# LiFePO4wered-USB.net
KiCad netlist of a schematic drawn in EAGLE
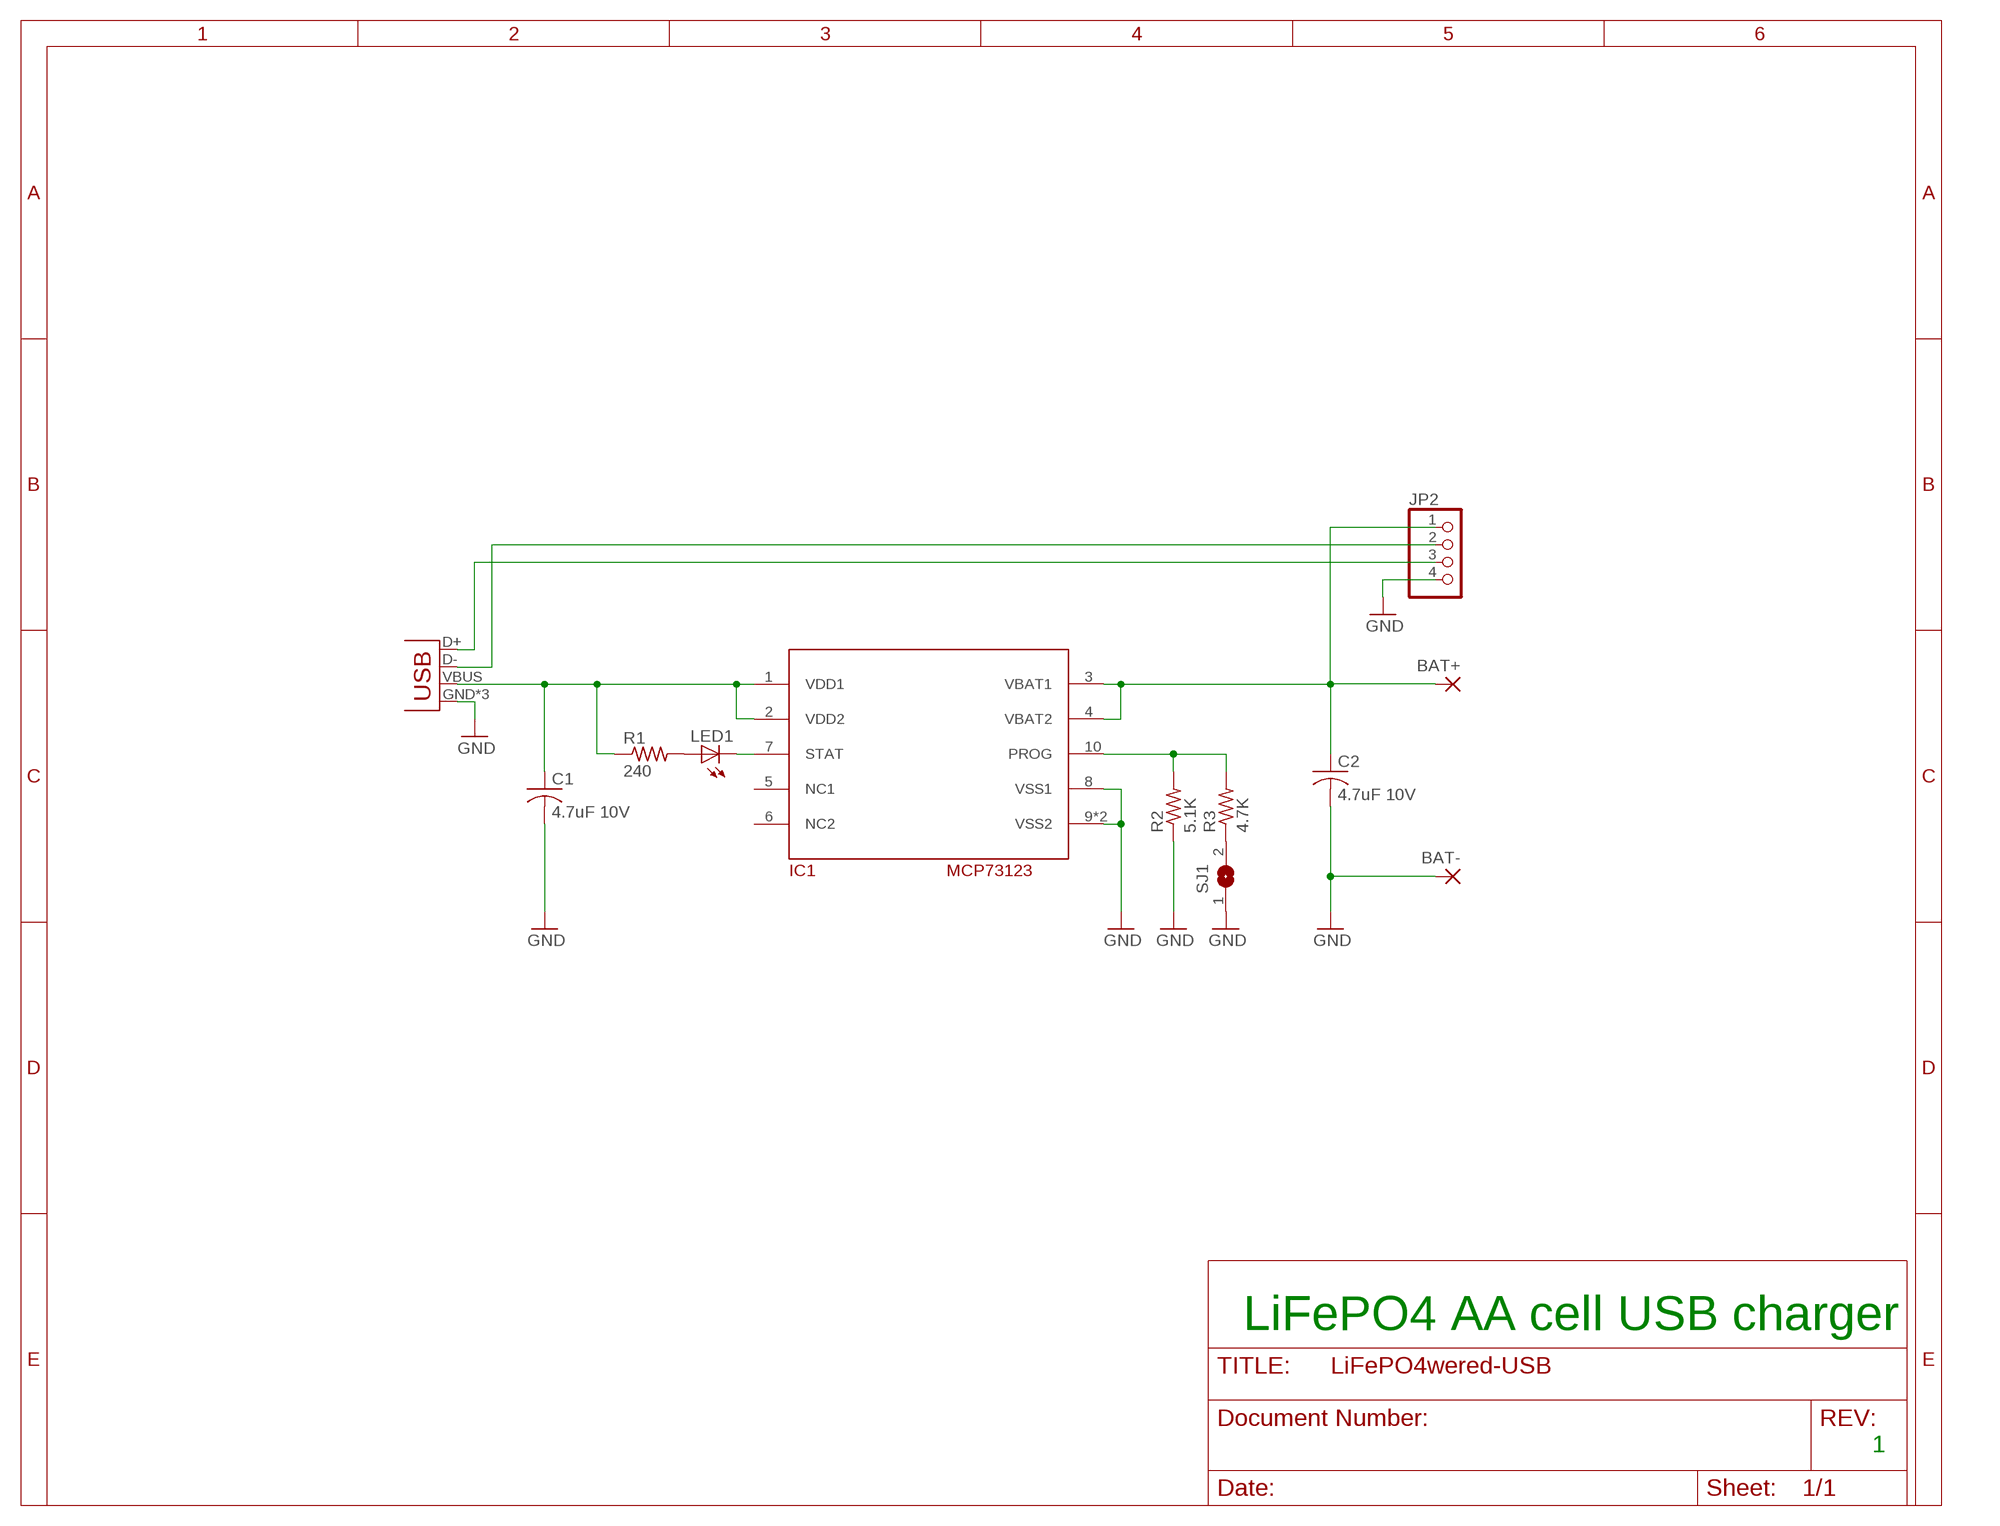
[diagram p0: schematic, sheet 1]

(export (version "E")
  (design (tool "Eeschema 10.0.6"))
  (components
    (comp (ref "BAT+")
      (value "2,54/1,0")
      (footprint "eagle-import:2,54_1,0")
      (libsource (lib "eagle-import") (part "2,54/1,0"))
    )
    (comp (ref "BAT-")
      (value "2,54/1,0")
      (footprint "eagle-import:2,54_1,0")
      (libsource (lib "eagle-import") (part "2,54/1,0"))
    )
    (comp (ref "C1")
      (value "4.7uF 10V")
      (footprint "eagle-import:C0603")
      (libsource (lib "eagle-import") (part "C-USC0603"))
    )
    (comp (ref "C2")
      (value "4.7uF 10V")
      (footprint "eagle-import:C0603")
      (libsource (lib "eagle-import") (part "C-USC0603"))
    )
    (comp (ref "IC1")
      (value "MCP73123")
      (footprint "eagle-import:DFN10-3X3")
      (libsource (lib "eagle-import") (part "MCP73123"))
    )
    (comp (ref "JP1")
      (value "USB-MICROB")
      (footprint "eagle-import:USB-MICROB")
      (libsource (lib "eagle-import") (part "USB-MICROB"))
    )
    (comp (ref "JP2")
      (value "PINHD-1X4")
      (footprint "eagle-import:1X04")
      (libsource (lib "eagle-import") (part "PINHD-1X4"))
    )
    (comp (ref "LED1")
      (value "LEDCHIP-LED0603")
      (footprint "eagle-import:CHIP-LED0603")
      (libsource (lib "eagle-import") (part "LEDCHIP-LED0603"))
    )
    (comp (ref "R1")
      (value "240")
      (footprint "eagle-import:R0603")
      (libsource (lib "eagle-import") (part "R-US_R0603"))
    )
    (comp (ref "R2")
      (value "5.1K")
      (footprint "eagle-import:R0603")
      (libsource (lib "eagle-import") (part "R-US_R0603"))
    )
    (comp (ref "R3")
      (value "4.7K")
      (footprint "eagle-import:R0603")
      (libsource (lib "eagle-import") (part "R-US_R0603"))
    )
    (comp (ref "SJ1") (value "SJ") (footprint "eagle-import:SJ") (libsource (lib "eagle-import") (part "SJ")))
  )
  (nets
    (net (code "1") (name "GND") (class "Default")
      (node (ref "BAT-") (pin "1") (pinfunction "P_1") (pintype "passive"))
      (node (ref "C1") (pin "2") (pinfunction "2_2") (pintype "passive"))
      (node (ref "C2") (pin "2") (pinfunction "2_2") (pintype "passive"))
      (node (ref "IC1") (pin "8") (pinfunction "VSS1_8") (pintype "bidirectional"))
      (node (ref "IC1") (pin "9") (pinfunction "VSS2_9") (pintype "bidirectional"))
      (node (ref "IC1") (pin "EXP") (pinfunction "VSS2_EXP") (pintype "bidirectional"))
      (node (ref "JP1") (pin "GND") (pinfunction "GND_GND") (pintype "bidirectional"))
      (node (ref "JP1") (pin "MT1") (pinfunction "GND_MT1") (pintype "bidirectional"))
      (node (ref "JP1") (pin "MT2") (pinfunction "GND_MT2") (pintype "bidirectional"))
      (node (ref "JP2") (pin "4") (pinfunction "4_4") (pintype "passive"))
      (node (ref "R2") (pin "1") (pinfunction "1_1") (pintype "passive"))
      (node (ref "SJ1") (pin "1") (pinfunction "1_1") (pintype "passive"))
    )
    (net (code "2") (name "Net-(BAT+-P)") (class "Default")
      (node (ref "BAT+") (pin "1") (pinfunction "P_1") (pintype "passive"))
      (node (ref "C2") (pin "1") (pinfunction "1_1") (pintype "passive"))
      (node (ref "IC1") (pin "3") (pinfunction "VBAT1_3") (pintype "bidirectional"))
      (node (ref "IC1") (pin "4") (pinfunction "VBAT2_4") (pintype "bidirectional"))
      (node (ref "JP2") (pin "1") (pinfunction "1_1") (pintype "passive"))
    )
    (net (code "3") (name "Net-(IC1-PROG)") (class "Default")
      (node (ref "IC1") (pin "10") (pinfunction "PROG_10") (pintype "bidirectional"))
      (node (ref "R2") (pin "2") (pinfunction "2_2") (pintype "passive"))
      (node (ref "R3") (pin "2") (pinfunction "2_2") (pintype "passive"))
    )
    (net (code "4") (name "Net-(IC1-STAT)") (class "Default")
      (node (ref "IC1") (pin "7") (pinfunction "STAT_7") (pintype "bidirectional"))
      (node (ref "LED1") (pin "C") (pinfunction "C_C") (pintype "passive"))
    )
    (net (code "5") (name "Net-(IC1-VDD1)") (class "Default")
      (node (ref "C1") (pin "1") (pinfunction "1_1") (pintype "passive"))
      (node (ref "IC1") (pin "1") (pinfunction "VDD1_1") (pintype "bidirectional"))
      (node (ref "IC1") (pin "2") (pinfunction "VDD2_2") (pintype "bidirectional"))
      (node (ref "JP1") (pin "VBUS") (pinfunction "VBUS_VBUS") (pintype "bidirectional"))
      (node (ref "R1") (pin "1") (pinfunction "1_1") (pintype "passive"))
    )
    (net (code "6") (name "Net-(JP1-PadD+)") (class "Default")
      (node (ref "JP1") (pin "D+") (pinfunction "D+_D+") (pintype "bidirectional"))
      (node (ref "JP2") (pin "3") (pinfunction "3_3") (pintype "passive"))
    )
    (net (code "7") (name "Net-(JP1-PadD-)") (class "Default")
      (node (ref "JP1") (pin "D-") (pinfunction "D-_D-") (pintype "bidirectional"))
      (node (ref "JP2") (pin "2") (pinfunction "2_2") (pintype "passive"))
    )
    (net (code "8") (name "Net-(LED1-PadA)") (class "Default")
      (node (ref "LED1") (pin "A") (pinfunction "A_A") (pintype "passive"))
      (node (ref "R1") (pin "2") (pinfunction "2_2") (pintype "passive"))
    )
    (net (code "9") (name "Net-(R3-Pad1)") (class "Default")
      (node (ref "R3") (pin "1") (pinfunction "1_1") (pintype "passive"))
      (node (ref "SJ1") (pin "2") (pinfunction "2_2") (pintype "passive"))
    )
    (net (code "10") (name "unconnected-(IC1-NC1-Pad5)") (class "Default")
      (node (ref "IC1") (pin "5") (pinfunction "NC1_5") (pintype "bidirectional"))
    )
    (net (code "11") (name "unconnected-(IC1-NC2-Pad6)") (class "Default")
      (node (ref "IC1") (pin "6") (pinfunction "NC2_6") (pintype "bidirectional"))
    )
  )
)
